# 04-POWERV2_2.net
KiCad netlist of a schematic drawn in Altium Designer
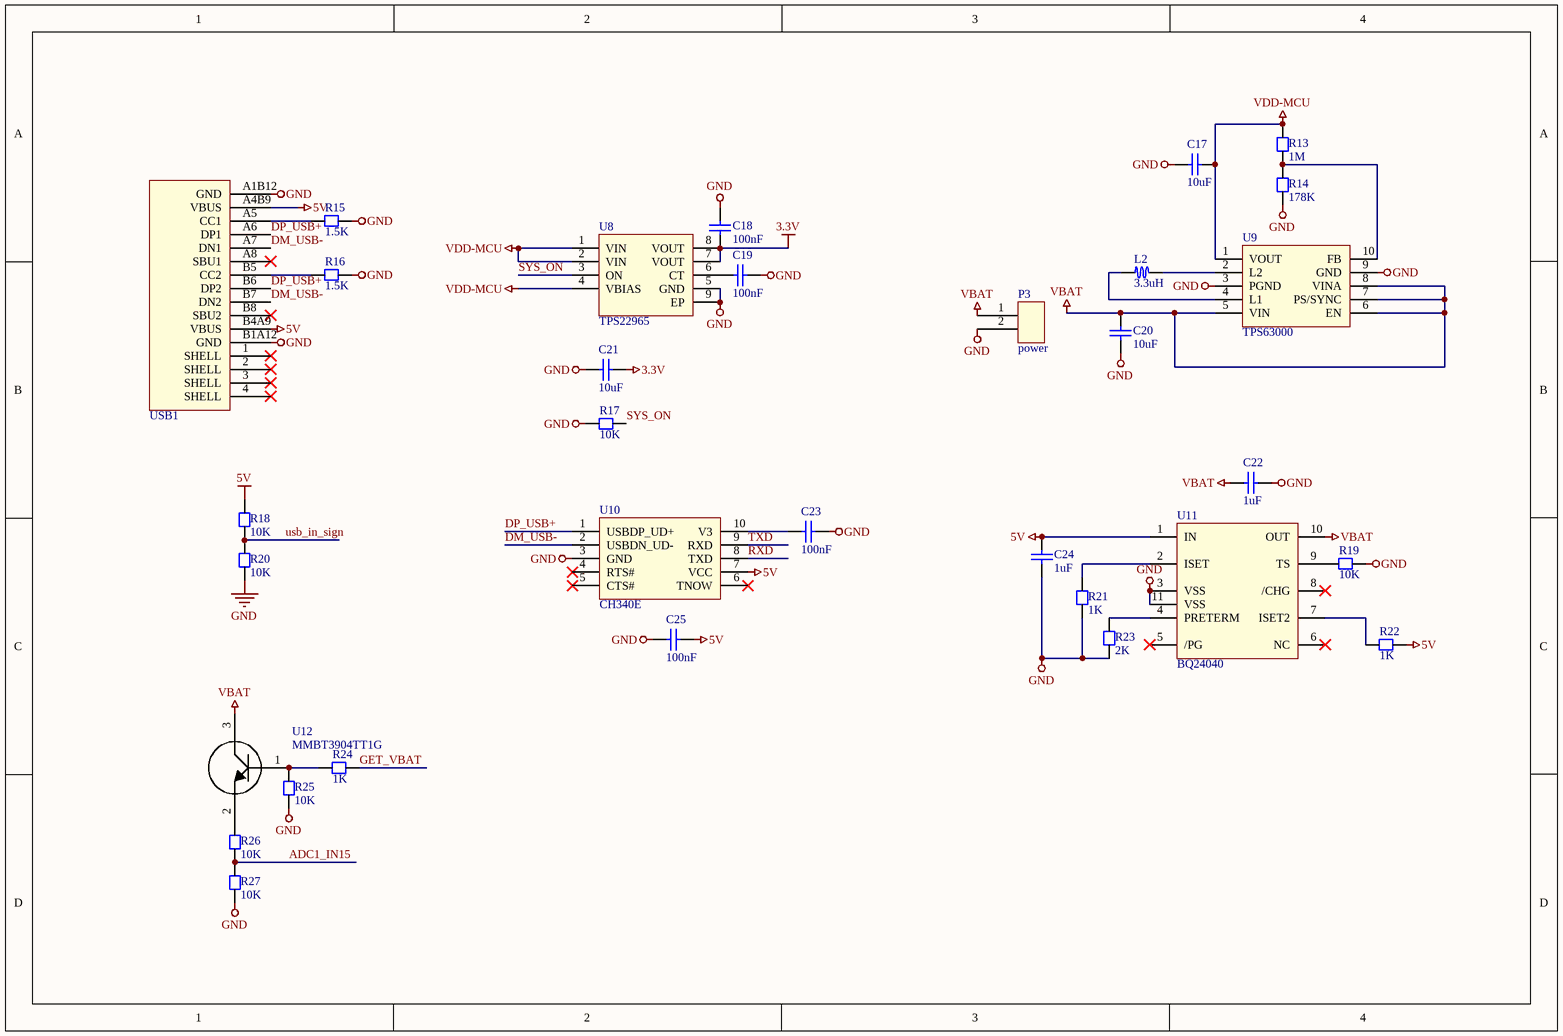
[diagram p0: 04-POWERV2.2.SchDoc]

(export (version "E")
  (design (tool "Eeschema 10.0.6"))
  (components
    (comp (ref "C17")
      (value "10uF")
      (footprint "CC1005-0402")
      (description "贴片电容")
      (libsource (lib "tianxiaohua_Schlib") (part "Chip capacitor"))
    )
    (comp (ref "C18")
      (value "100nF")
      (footprint "CC1005-0402")
      (description "贴片电容")
      (libsource (lib "tianxiaohua_Schlib") (part "Chip capacitor"))
    )
    (comp (ref "C19")
      (value "100nF")
      (footprint "CC1005-0402")
      (description "贴片电容")
      (libsource (lib "tianxiaohua_Schlib") (part "Chip capacitor"))
    )
    (comp (ref "C20")
      (value "10uF")
      (footprint "CC1005-0402")
      (description "贴片电容")
      (libsource (lib "tianxiaohua_Schlib") (part "Chip capacitor"))
    )
    (comp (ref "C21")
      (value "10uF")
      (footprint "CC1005-0402")
      (description "贴片电容")
      (libsource (lib "tianxiaohua_Schlib") (part "Chip capacitor"))
    )
    (comp (ref "C22")
      (value "1uF")
      (footprint "CC1005-0402")
      (description "贴片电容")
      (libsource (lib "tianxiaohua_Schlib") (part "Chip capacitor"))
    )
    (comp (ref "C23")
      (value "100nF")
      (footprint "CC1005-0402")
      (description "贴片电容")
      (libsource (lib "tianxiaohua_Schlib") (part "Chip capacitor"))
    )
    (comp (ref "C24")
      (value "1uF")
      (footprint "CC1005-0402")
      (description "贴片电容")
      (libsource (lib "tianxiaohua_Schlib") (part "Chip capacitor"))
    )
    (comp (ref "C25")
      (value "100nF")
      (footprint "CC1005-0402")
      (description "贴片电容")
      (libsource (lib "tianxiaohua_Schlib") (part "Chip capacitor"))
    )
    (comp (ref "L2")
      (value "3.3uH")
      (footprint "Inductor-0805")
      (description "贴片电感")
      (libsource (lib "tianxiaohua_Schlib") (part "Chip inductor"))
    )
    (comp (ref "P3")
      (value "power")
      (footprint "POWER-3.7V")
      (libsource (lib "tianxiaohua_Schlib") (part "power"))
    )
    (comp (ref "R13")
      (value "1M")
      (footprint "CR1005-0402")
      (description "贴片电阻")
      (libsource (lib "") (part "Chip resistor_1"))
    )
    (comp (ref "R14")
      (value "178K")
      (footprint "CR1005-0402")
      (description "贴片电阻")
      (libsource (lib "tianxiaohua_Schlib") (part "Chip resistor"))
    )
    (comp (ref "R15")
      (value "1.5K")
      (footprint "CR1005-0402")
      (description "贴片电阻")
      (libsource (lib "") (part "Chip resistor_3"))
    )
    (comp (ref "R16")
      (value "1.5K")
      (footprint "CR1005-0402")
      (description "贴片电阻")
      (libsource (lib "") (part "Chip resistor_3"))
    )
    (comp (ref "R17")
      (value "10K")
      (footprint "CR1005-0402")
      (description "贴片电阻")
      (libsource (lib "") (part "Chip resistor_3"))
    )
    (comp (ref "R18")
      (value "10K")
      (footprint "CR1005-0402")
      (description "贴片电阻")
      (libsource (lib "") (part "Chip resistor_1"))
    )
    (comp (ref "R19")
      (value "10K")
      (footprint "CR1005-0402")
      (description "贴片电阻")
      (libsource (lib "") (part "Chip resistor_2"))
    )
    (comp (ref "R20")
      (value "10K")
      (footprint "CR1005-0402")
      (description "贴片电阻")
      (libsource (lib "") (part "Chip resistor_1"))
    )
    (comp (ref "R21")
      (value "1K")
      (footprint "CR1005-0402")
      (description "贴片电阻")
      (libsource (lib "") (part "Chip resistor_1"))
    )
    (comp (ref "R22")
      (value "1K")
      (footprint "CR1005-0402")
      (description "贴片电阻")
      (libsource (lib "") (part "Chip resistor_2"))
    )
    (comp (ref "R23")
      (value "2K")
      (footprint "CR1005-0402")
      (description "贴片电阻")
      (libsource (lib "") (part "Chip resistor_1"))
    )
    (comp (ref "R24")
      (value "1K")
      (footprint "CR1005-0402")
      (description "贴片电阻")
      (libsource (lib "") (part "Chip resistor_2"))
    )
    (comp (ref "R25")
      (value "10K")
      (footprint "CR1005-0402")
      (description "贴片电阻")
      (libsource (lib "") (part "Chip resistor_1"))
    )
    (comp (ref "R26")
      (value "10K")
      (footprint "CR1005-0402")
      (description "贴片电阻")
      (libsource (lib "") (part "Chip resistor_1"))
    )
    (comp (ref "R27")
      (value "10K")
      (footprint "CR1005-0402")
      (description "贴片电阻")
      (libsource (lib "") (part "Chip resistor_1"))
    )
    (comp (ref "U8")
      (value "TPS22965")
      (footprint "UDFN-8")
      (description "DFN-8 功率开关芯片 TPS22965DSGR")
      (libsource (lib "tianxiaohua_Schlib") (part "TPS22965"))
    )
    (comp (ref "U9")
      (value "TPS63000")
      (footprint "SON10")
      (description "宽电压电源转换芯片输出3.3V输入1V至6V")
      (libsource (lib "tianxiaohua_Schlib") (part "TPS63000"))
    )
    (comp (ref "U10")
      (value "CH340E")
      (footprint "MSOP-10")
      (description "usd转串口芯片 MSOP10封装")
      (libsource (lib "tianxiaohua_Schlib") (part "CH340E"))
    )
    (comp (ref "U11")
      (value "BQ24040")
      (footprint "WSON-10_L2.0-W2.0-P0.40-BL-EP")
      (description "1A 具有自动启动功能的单输入，单节锂离子和锂聚合物电池充电\r\n器")
      (libsource (lib "tianxiaohua_Schlib") (part "BQ24041"))
    )
    (comp (ref "U12")
      (value "MMBT3904TT1G")
      (footprint "SOT-416")
      (description "NPN 电流 - 集电极（Ic）（最大值）：200mA 电压 - 集射极击穿（最大值）：40V SOT-23-3")
      (libsource (lib "tianxiaohua_Schlib") (part "MMBT3904TT1G"))
    )
    (comp (ref "USB1")
      (value "Tpye-c 16P")
      (footprint "TYPE-C 16P")
      (description "16P 封装的TYPE -c接口 4固定插脚 双向")
      (libsource (lib "tianxiaohua_Schlib") (part "Tpye-c 16P"))
    )
  )
  (nets
    (net (code "1") (name "/ADC1_IN15") (class "Default")
      (node (ref "R26") (pin "2") (pinfunction "2_2") (pintype "passive"))
      (node (ref "R27") (pin "1") (pinfunction "1_1") (pintype "passive"))
    )
    (net (code "2") (name "/DM_USB-") (class "Default")
      (node (ref "U10") (pin "2") (pinfunction "USBDN_UD-_2") (pintype "passive"))
      (node (ref "USB1") (pin "A7") (pinfunction "DN1_A7") (pintype "power_in"))
      (node (ref "USB1") (pin "B7") (pinfunction "DN2_B7") (pintype "power_in"))
    )
    (net (code "3") (name "/DP_USB+") (class "Default")
      (node (ref "U10") (pin "1") (pinfunction "USBDP_UD+_1") (pintype "passive"))
      (node (ref "USB1") (pin "A6") (pinfunction "DP1_A6") (pintype "power_in"))
      (node (ref "USB1") (pin "B6") (pinfunction "DP2_B6") (pintype "power_in"))
    )
    (net (code "4") (name "/GET_VBAT") (class "Default")
      (node (ref "R24") (pin "2") (pinfunction "2_2") (pintype "passive"))
    )
    (net (code "5") (name "/RXD") (class "Default")
      (node (ref "U10") (pin "8") (pinfunction "TXD_8") (pintype "passive"))
    )
    (net (code "6") (name "/SYS_ON") (class "Default")
      (node (ref "R17") (pin "1") (pinfunction "1_1") (pintype "passive"))
      (node (ref "U8") (pin "3") (pinfunction "ON_3") (pintype "passive"))
    )
    (net (code "7") (name "/TXD") (class "Default")
      (node (ref "U10") (pin "9") (pinfunction "RXD_9") (pintype "passive"))
    )
    (net (code "8") (name "/usb_in_sign") (class "Default")
      (node (ref "R18") (pin "2") (pinfunction "2_2") (pintype "passive"))
      (node (ref "R20") (pin "1") (pinfunction "1_1") (pintype "passive"))
    )
    (net (code "9") (name "3.3V") (class "Default")
      (node (ref "C18") (pin "1") (pinfunction "1_1") (pintype "passive"))
      (node (ref "C21") (pin "2") (pinfunction "2_2") (pintype "passive"))
      (node (ref "U8") (pin "7") (pinfunction "VOUT_7") (pintype "passive"))
      (node (ref "U8") (pin "8") (pinfunction "VOUT_8") (pintype "passive"))
    )
    (net (code "10") (name "5V") (class "Default")
      (node (ref "C24") (pin "1") (pinfunction "1_1") (pintype "passive"))
      (node (ref "C25") (pin "2") (pinfunction "2_2") (pintype "passive"))
      (node (ref "R18") (pin "1") (pinfunction "1_1") (pintype "passive"))
      (node (ref "R22") (pin "2") (pinfunction "2_2") (pintype "passive"))
      (node (ref "U10") (pin "7") (pinfunction "VCC_7") (pintype "passive"))
      (node (ref "U11") (pin "1") (pinfunction "IN_1") (pintype "passive"))
      (node (ref "USB1") (pin "A4B9") (pinfunction "VBUS_A4B9") (pintype "power_in"))
      (node (ref "USB1") (pin "B4A9") (pinfunction "VBUS_B4A9") (pintype "power_in"))
    )
    (net (code "11") (name "GND") (class "Default")
      (node (ref "C17") (pin "1") (pinfunction "1_1") (pintype "passive"))
      (node (ref "C18") (pin "2") (pinfunction "2_2") (pintype "passive"))
      (node (ref "C19") (pin "1") (pinfunction "1_1") (pintype "passive"))
      (node (ref "C20") (pin "1") (pinfunction "1_1") (pintype "passive"))
      (node (ref "C21") (pin "1") (pinfunction "1_1") (pintype "passive"))
      (node (ref "C22") (pin "1") (pinfunction "1_1") (pintype "passive"))
      (node (ref "C23") (pin "2") (pinfunction "2_2") (pintype "passive"))
      (node (ref "C24") (pin "2") (pinfunction "2_2") (pintype "passive"))
      (node (ref "C25") (pin "1") (pinfunction "1_1") (pintype "passive"))
      (node (ref "P3") (pin "2") (pinfunction "2_2") (pintype "passive"))
      (node (ref "R14") (pin "1") (pinfunction "1_1") (pintype "passive"))
      (node (ref "R15") (pin "1") (pinfunction "1_1") (pintype "passive"))
      (node (ref "R16") (pin "1") (pinfunction "1_1") (pintype "passive"))
      (node (ref "R17") (pin "2") (pinfunction "2_2") (pintype "passive"))
      (node (ref "R19") (pin "2") (pinfunction "2_2") (pintype "passive"))
      (node (ref "R20") (pin "2") (pinfunction "2_2") (pintype "passive"))
      (node (ref "R21") (pin "2") (pinfunction "2_2") (pintype "passive"))
      (node (ref "R23") (pin "2") (pinfunction "2_2") (pintype "passive"))
      (node (ref "R25") (pin "2") (pinfunction "2_2") (pintype "passive"))
      (node (ref "R27") (pin "2") (pinfunction "2_2") (pintype "passive"))
      (node (ref "U10") (pin "3") (pinfunction "GND_3") (pintype "passive"))
      (node (ref "U11") (pin "11") (pinfunction "VSS_11") (pintype "passive"))
      (node (ref "U11") (pin "3") (pinfunction "VSS_3") (pintype "passive"))
      (node (ref "U8") (pin "5") (pinfunction "GND_5") (pintype "passive"))
      (node (ref "U8") (pin "9") (pinfunction "EP_9") (pintype "passive"))
      (node (ref "U9") (pin "3") (pinfunction "PGND_3") (pintype "passive"))
      (node (ref "U9") (pin "9") (pinfunction "GND_9") (pintype "passive"))
      (node (ref "USB1") (pin "A1B12") (pinfunction "GND_A1B12") (pintype "power_in"))
      (node (ref "USB1") (pin "B1A12") (pinfunction "GND_B1A12") (pintype "power_in"))
    )
    (net (code "12") (name "Net-(R24-Pad1)") (class "Default")
      (node (ref "R24") (pin "1") (pinfunction "1_1") (pintype "passive"))
      (node (ref "R25") (pin "1") (pinfunction "1_1") (pintype "passive"))
      (node (ref "U12") (pin "1") (pinfunction "1_1") (pintype "passive"))
    )
    (net (code "13") (name "Net-(R26-Pad1)") (class "Default")
      (node (ref "R26") (pin "1") (pinfunction "1_1") (pintype "passive"))
      (node (ref "U12") (pin "2") (pinfunction "2_2") (pintype "passive"))
    )
    (net (code "14") (name "Net-(U8-CT)") (class "Default")
      (node (ref "C19") (pin "2") (pinfunction "2_2") (pintype "passive"))
      (node (ref "U8") (pin "6") (pinfunction "CT_6") (pintype "passive"))
    )
    (net (code "15") (name "Net-(U9-FB)") (class "Default")
      (node (ref "R13") (pin "2") (pinfunction "2_2") (pintype "passive"))
      (node (ref "R14") (pin "2") (pinfunction "2_2") (pintype "passive"))
      (node (ref "U9") (pin "10") (pinfunction "FB_10") (pintype "passive"))
    )
    (net (code "16") (name "Net-(U9-L1)") (class "Default")
      (node (ref "L2") (pin "1") (pinfunction "1_1") (pintype "passive"))
      (node (ref "U9") (pin "4") (pinfunction "L1_4") (pintype "passive"))
    )
    (net (code "17") (name "Net-(U9-L2)") (class "Default")
      (node (ref "L2") (pin "2") (pinfunction "2_2") (pintype "passive"))
      (node (ref "U9") (pin "2") (pinfunction "L2_2") (pintype "passive"))
    )
    (net (code "18") (name "Net-(U10-V3)") (class "Default")
      (node (ref "C23") (pin "1") (pinfunction "1_1") (pintype "passive"))
      (node (ref "U10") (pin "10") (pinfunction "V3_10") (pintype "passive"))
    )
    (net (code "19") (name "Net-(U11-ISET)") (class "Default")
      (node (ref "R21") (pin "1") (pinfunction "1_1") (pintype "passive"))
      (node (ref "U11") (pin "2") (pinfunction "ISET_2") (pintype "passive"))
    )
    (net (code "20") (name "Net-(U11-ISET2)") (class "Default")
      (node (ref "R22") (pin "1") (pinfunction "1_1") (pintype "passive"))
      (node (ref "U11") (pin "7") (pinfunction "ISET2_7") (pintype "passive"))
    )
    (net (code "21") (name "Net-(U11-PRETERM)") (class "Default")
      (node (ref "R23") (pin "1") (pinfunction "1_1") (pintype "passive"))
      (node (ref "U11") (pin "4") (pinfunction "PRETERM_4") (pintype "passive"))
    )
    (net (code "22") (name "Net-(U11-TS)") (class "Default")
      (node (ref "R19") (pin "1") (pinfunction "1_1") (pintype "passive"))
      (node (ref "U11") (pin "9") (pinfunction "TS_9") (pintype "passive"))
    )
    (net (code "23") (name "Net-(USB1-CC1)") (class "Default")
      (node (ref "R15") (pin "2") (pinfunction "2_2") (pintype "passive"))
      (node (ref "USB1") (pin "A5") (pinfunction "CC1_A5") (pintype "power_in"))
    )
    (net (code "24") (name "Net-(USB1-CC2)") (class "Default")
      (node (ref "R16") (pin "2") (pinfunction "2_2") (pintype "passive"))
      (node (ref "USB1") (pin "B5") (pinfunction "CC2_B5") (pintype "power_in"))
    )
    (net (code "25") (name "VBAT") (class "Default")
      (node (ref "C20") (pin "2") (pinfunction "2_2") (pintype "passive"))
      (node (ref "C22") (pin "2") (pinfunction "2_2") (pintype "passive"))
      (node (ref "P3") (pin "1") (pinfunction "1_1") (pintype "passive"))
      (node (ref "U11") (pin "10") (pinfunction "OUT_10") (pintype "passive"))
      (node (ref "U12") (pin "3") (pinfunction "3_3") (pintype "passive"))
      (node (ref "U9") (pin "5") (pinfunction "VIN_5") (pintype "passive"))
      (node (ref "U9") (pin "6") (pinfunction "EN_6") (pintype "passive"))
      (node (ref "U9") (pin "7") (pinfunction "PS/SYNC_7") (pintype "passive"))
      (node (ref "U9") (pin "8") (pinfunction "VINA_8") (pintype "passive"))
    )
    (net (code "26") (name "VDD-MCU") (class "Default")
      (node (ref "C17") (pin "2") (pinfunction "2_2") (pintype "passive"))
      (node (ref "R13") (pin "1") (pinfunction "1_1") (pintype "passive"))
      (node (ref "U8") (pin "1") (pinfunction "VIN_1") (pintype "passive"))
      (node (ref "U8") (pin "2") (pinfunction "VIN_2") (pintype "passive"))
      (node (ref "U8") (pin "4") (pinfunction "VBIAS_4") (pintype "passive"))
      (node (ref "U9") (pin "1") (pinfunction "VOUT_1") (pintype "passive"))
    )
    (net (code "27") (name "unconnected-(U10-CTS#-Pad5)") (class "Default")
      (node (ref "U10") (pin "5") (pinfunction "CTS#_5") (pintype "passive+no_connect"))
    )
    (net (code "28") (name "unconnected-(U10-RTS#-Pad4)") (class "Default")
      (node (ref "U10") (pin "4") (pinfunction "RTS#_4") (pintype "passive+no_connect"))
    )
    (net (code "29") (name "unconnected-(U10-TNOW-Pad6)") (class "Default")
      (node (ref "U10") (pin "6") (pinfunction "TNOW_6") (pintype "passive+no_connect"))
    )
    (net (code "30") (name "unconnected-(U11-NC-Pad6)") (class "Default")
      (node (ref "U11") (pin "6") (pinfunction "NC_6") (pintype "passive+no_connect"))
    )
    (net (code "31") (name "unconnected-(U11-{slash}CHG-Pad8)") (class "Default")
      (node (ref "U11") (pin "8") (pinfunction "/CHG_8") (pintype "passive+no_connect"))
    )
    (net (code "32") (name "unconnected-(U11-{slash}PG-Pad5)") (class "Default")
      (node (ref "U11") (pin "5") (pinfunction "/PG_5") (pintype "passive+no_connect"))
    )
    (net (code "33") (name "unconnected-(USB1-SBU1-PadA8)") (class "Default")
      (node (ref "USB1") (pin "A8") (pinfunction "SBU1_A8") (pintype "power_in+no_connect"))
    )
    (net (code "34") (name "unconnected-(USB1-SBU2-PadB8)") (class "Default")
      (node (ref "USB1") (pin "B8") (pinfunction "SBU2_B8") (pintype "power_in+no_connect"))
    )
    (net (code "35") (name "unconnected-(USB1-SHELL-Pad1)") (class "Default")
      (node (ref "USB1") (pin "1") (pinfunction "SHELL_1") (pintype "power_in+no_connect"))
    )
    (net (code "36") (name "unconnected-(USB1-SHELL-Pad2)") (class "Default")
      (node (ref "USB1") (pin "2") (pinfunction "SHELL_2") (pintype "power_in+no_connect"))
    )
    (net (code "37") (name "unconnected-(USB1-SHELL-Pad3)") (class "Default")
      (node (ref "USB1") (pin "3") (pinfunction "SHELL_3") (pintype "power_in+no_connect"))
    )
    (net (code "38") (name "unconnected-(USB1-SHELL-Pad4)") (class "Default")
      (node (ref "USB1") (pin "4") (pinfunction "SHELL_4") (pintype "power_in+no_connect"))
    )
  )
)
